# sch.net
KiCad netlist of a schematic drawn in Altium Designer
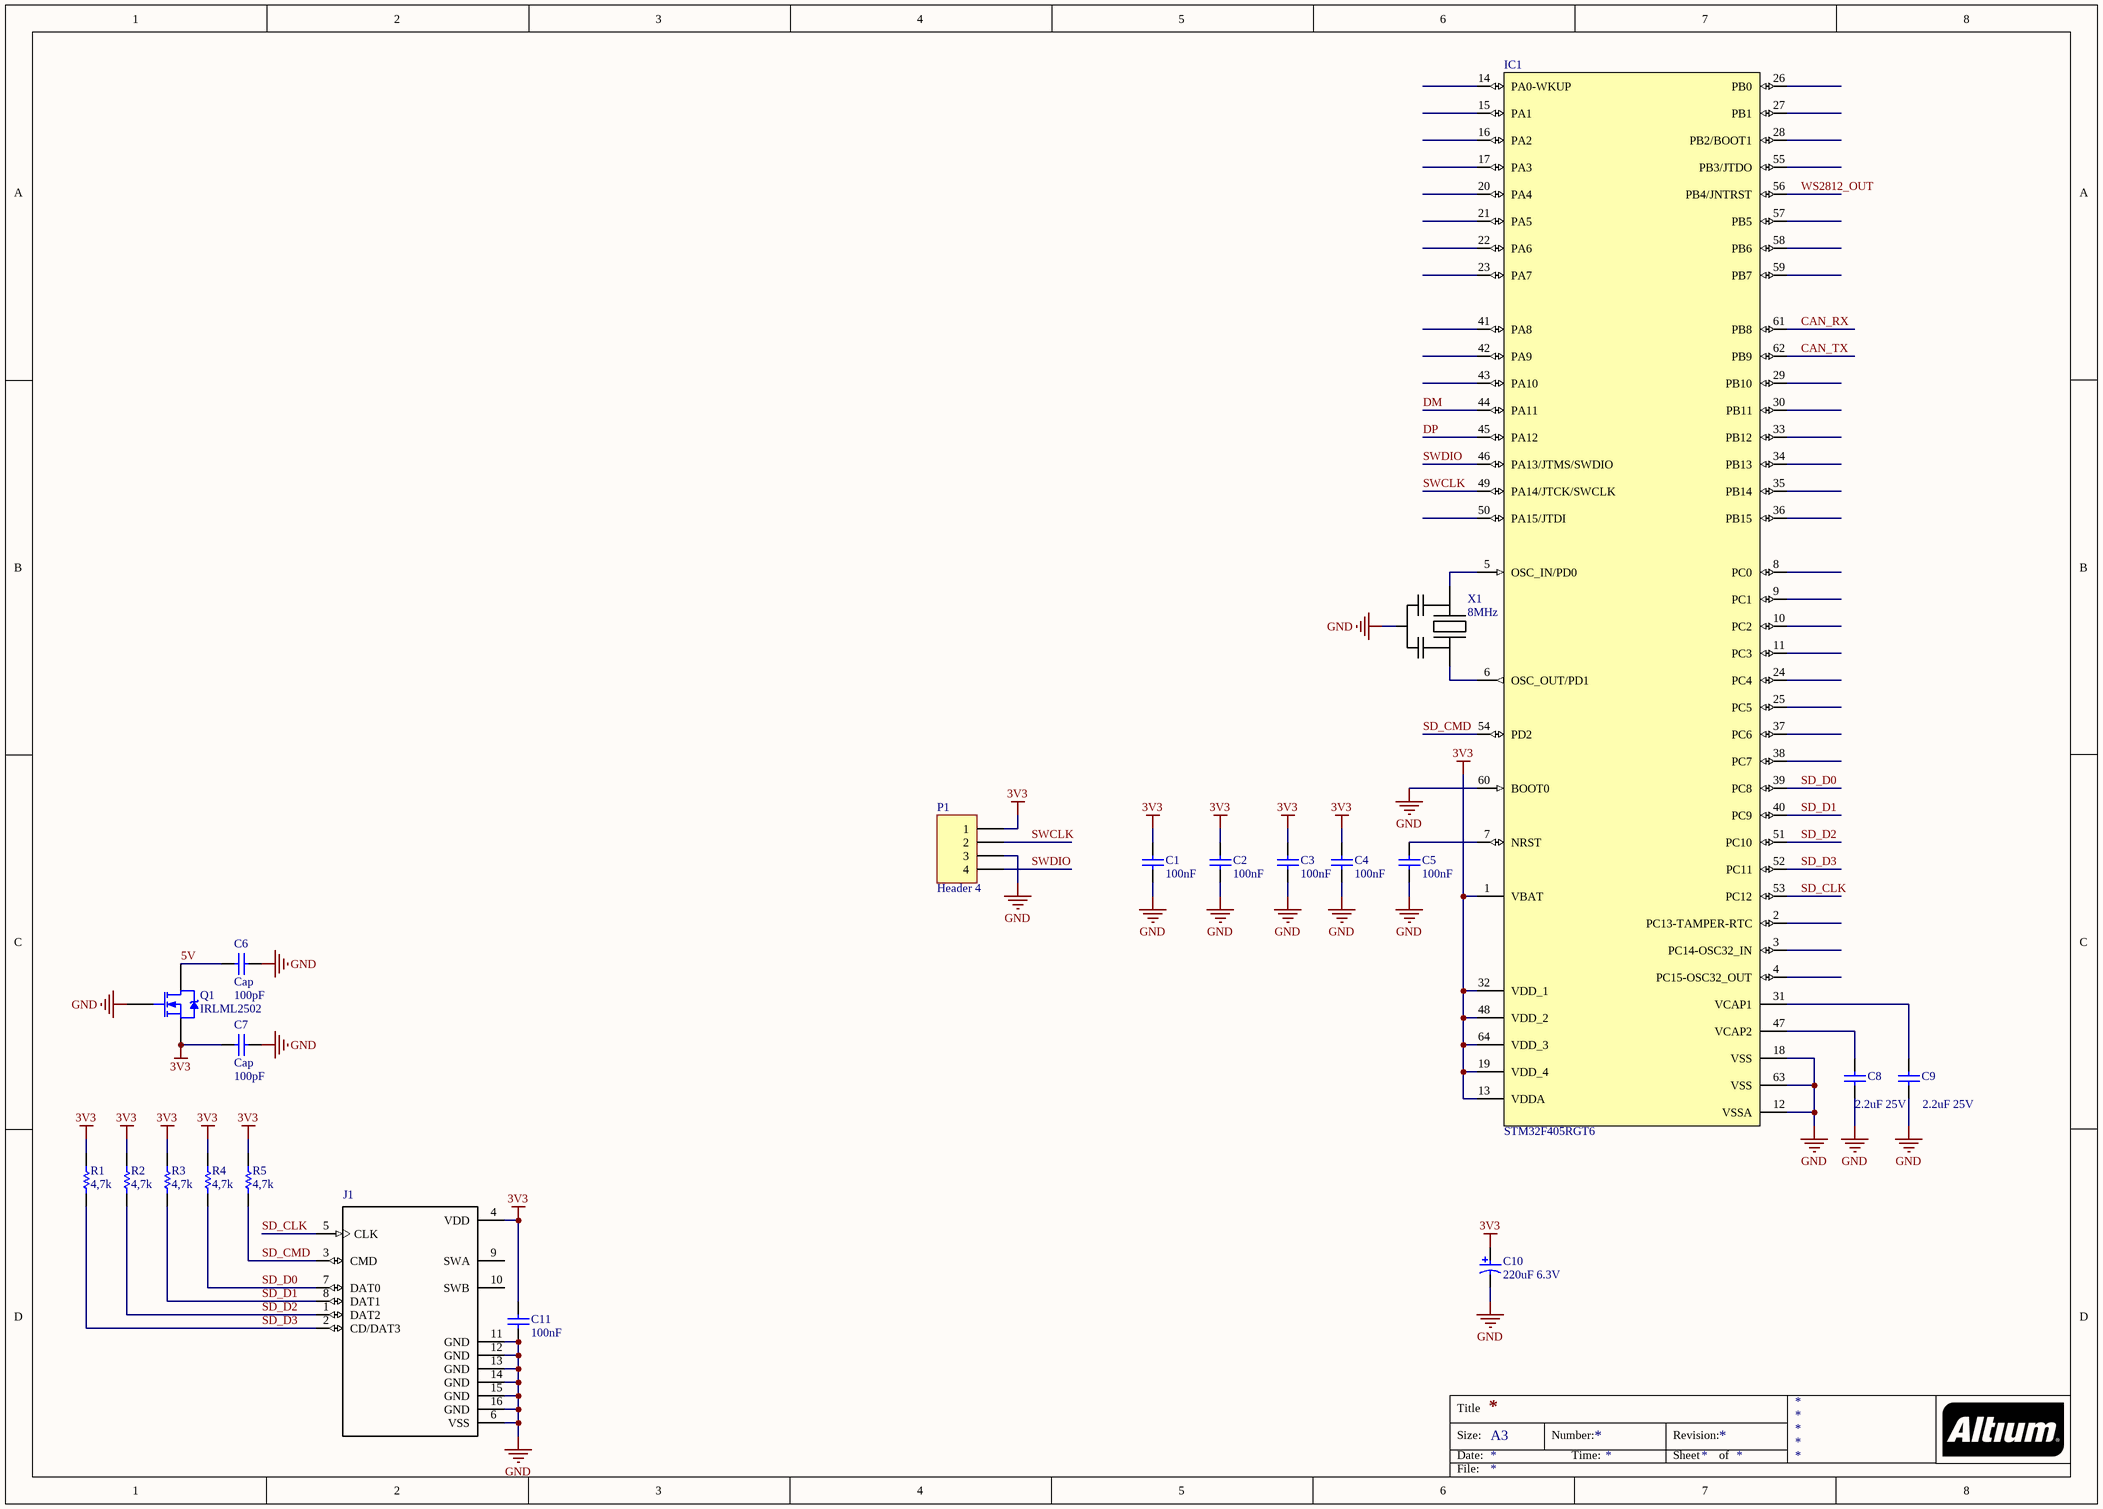
[diagram p0: sch.SchDoc]

(export (version "E")
  (design (tool "Eeschema 10.0.6"))
  (components
    (comp (ref "C1")
      (value "100nF")
      (footprint "RR_0603")
      (description "CAPACITOR CHIP")
      (fields (field (name "MANUFACTURER") "Vishay Vitramon"))
      (libsource (lib "RozumLibrary") (part "CAP-0603-104-25V"))
    )
    (comp (ref "C2")
      (value "100nF")
      (footprint "RR_0603")
      (description "CAPACITOR CHIP")
      (fields (field (name "MANUFACTURER") "Vishay Vitramon"))
      (libsource (lib "RozumLibrary") (part "CAP-0603-104-25V"))
    )
    (comp (ref "C3")
      (value "100nF")
      (footprint "RR_0603")
      (description "CAPACITOR CHIP")
      (fields (field (name "MANUFACTURER") "Vishay Vitramon"))
      (libsource (lib "RozumLibrary") (part "CAP-0603-104-25V"))
    )
    (comp (ref "C4")
      (value "100nF")
      (footprint "RR_0603")
      (description "CAPACITOR CHIP")
      (fields (field (name "MANUFACTURER") "Vishay Vitramon"))
      (libsource (lib "RozumLibrary") (part "CAP-0603-104-25V"))
    )
    (comp (ref "C5")
      (value "100nF")
      (footprint "RR_0603")
      (description "CAPACITOR CHIP")
      (fields (field (name "MANUFACTURER") "Vishay Vitramon"))
      (libsource (lib "RozumLibrary") (part "CAP-0603-104-25V"))
    )
    (comp (ref "C6")
      (value "Cap")
      (footprint "RC_1210_T1.8")
      (description "Capacitor")
      (fields (field (name "ALTIUM_VALUE") "100pF") (field (name "PUBLISHER") "Altium Limited"))
      (libsource (lib "Miscellaneous Devices") (part "Cap"))
    )
    (comp (ref "C7")
      (value "Cap")
      (footprint "RC_1210_T1.8")
      (description "Capacitor")
      (fields (field (name "ALTIUM_VALUE") "100pF") (field (name "PUBLISHER") "Altium Limited"))
      (libsource (lib "Miscellaneous Devices") (part "Cap"))
    )
    (comp (ref "C8")
      (value "2.2uF 25V")
      (footprint "RC_0603")
      (description "CAPACITOR CHIP")
      (fields (field (name "MANUFACTURER") "Murata"))
      (libsource (lib "RozumLibrary") (part "CAP-0603-225-25V"))
    )
    (comp (ref "C9")
      (value "2.2uF 25V")
      (footprint "RC_0603")
      (description "CAPACITOR CHIP")
      (fields (field (name "MANUFACTURER") "Murata"))
      (libsource (lib "RozumLibrary") (part "CAP-0603-225-25V"))
    )
    (comp (ref "C10")
      (value "220uF 6.3V")
      (footprint "RR_CAP-C")
      (description "CAPACITOR TANTAL CASE C")
      (fields (field (name "MANUFACTURER") "KEMET"))
      (libsource (lib "RozumLibrary") (part "CAP-TANT-C-227-6.3V"))
    )
    (comp (ref "C11")
      (value "100nF")
      (footprint "RR_0603")
      (description "CAPACITOR CHIP")
      (fields (field (name "MANUFACTURER") "Vishay Vitramon"))
      (libsource (lib "RozumLibrary") (part "CAP-0603-104-25V"))
    )
    (comp (ref "IC1")
      (value "STM32F405RGT6")
      (footprint "RR_LQFP-64_L_ROUND")
      (description "STM32 ARM-based 32-bit MCU")
      (fields (field (name "MANUFACTURER") "STMicroelectronics"))
      (libsource (lib "RozumLibrary") (part "STM32F405RGT6_RR"))
    )
    (comp (ref "J1")
      (value "MICROSD_2201778-1")
      (footprint "RR_CONN_MICROSD_TE_2201778-1")
      (description "MICRO SD PUSH PUSH LOW PROFILE TYPE")
      (fields (field (name "MANUFACTURER") "TE Connectivity AMP Connectors"))
      (libsource (lib "Schlib1") (part "MICROSD_2201778-1"))
    )
    (comp (ref "P1")
      (value "Header 4")
      (footprint "MHDR1X4")
      (description "Header, 4-Pin")
      (libsource (lib "Miscellaneous Connectors") (part "Header 4"))
    )
    (comp (ref "Q1")
      (value "IRLML2502")
      (footprint "RR_SOT-23")
      (description "MOSFET N-CH 20V 4.2A SOT-23-3")
      (fields (field (name "MANUFACTURER") "Infineon Technologies"))
      (libsource (lib "RozumLibrary") (part "IRLML2502"))
    )
    (comp (ref "R1")
      (value "4,7k")
      (footprint "RR_0603")
      (description "RESISTOR")
      (fields (field (name "MANUFACTURER") "Panasonic Electronic Components"))
      (libsource (lib "RozumLibrary") (part "RES-0603-4K7-5%"))
    )
    (comp (ref "R2")
      (value "4,7k")
      (footprint "RR_0603")
      (description "RESISTOR")
      (fields (field (name "MANUFACTURER") "Panasonic Electronic Components"))
      (libsource (lib "RozumLibrary") (part "RES-0603-4K7-5%"))
    )
    (comp (ref "R3")
      (value "4,7k")
      (footprint "RR_0603")
      (description "RESISTOR")
      (fields (field (name "MANUFACTURER") "Panasonic Electronic Components"))
      (libsource (lib "RozumLibrary") (part "RES-0603-4K7-5%"))
    )
    (comp (ref "R4")
      (value "4,7k")
      (footprint "RR_0603")
      (description "RESISTOR")
      (fields (field (name "MANUFACTURER") "Panasonic Electronic Components"))
      (libsource (lib "RozumLibrary") (part "RES-0603-4K7-5%"))
    )
    (comp (ref "R5")
      (value "4,7k")
      (footprint "RR_0603")
      (description "RESISTOR")
      (fields (field (name "MANUFACTURER") "Panasonic Electronic Components"))
      (libsource (lib "RozumLibrary") (part "RES-0603-4K7-5%"))
    )
    (comp (ref "X1")
      (value "8MHz")
      (footprint "RR_CRYSTAL_3.2X1.3")
      (description "XTAL 8.0000MHZ 33PF SMD")
      (fields (field (name "MANUFACTURER") "Murata Electronics"))
      (libsource (lib "RozumLibrary") (part "CSTCE8M00G55-R0"))
    )
  )
  (nets
    (net (code "1") (name "/5V") (class "Default")
      (node (ref "C6") (pin "2") (pinfunction "2_2") (pintype "passive"))
      (node (ref "Q1") (pin "3") (pinfunction "D_3") (pintype "passive"))
    )
    (net (code "2") (name "/CAN_RX") (class "Default")
      (node (ref "IC1") (pin "61") (pinfunction "PB8_61") (pintype "bidirectional"))
    )
    (net (code "3") (name "/CAN_TX") (class "Default")
      (node (ref "IC1") (pin "62") (pinfunction "PB9_62") (pintype "bidirectional"))
    )
    (net (code "4") (name "/DM") (class "Default")
      (node (ref "IC1") (pin "44") (pinfunction "PA11_44") (pintype "bidirectional"))
    )
    (net (code "5") (name "/DP") (class "Default")
      (node (ref "IC1") (pin "45") (pinfunction "PA12_45") (pintype "bidirectional"))
    )
    (net (code "6") (name "/SD_CLK") (class "Default")
      (node (ref "IC1") (pin "53") (pinfunction "PC12_53") (pintype "bidirectional"))
      (node (ref "J1") (pin "5") (pinfunction "CLK_5") (pintype "input"))
    )
    (net (code "7") (name "/SD_CMD") (class "Default")
      (node (ref "IC1") (pin "54") (pinfunction "PD2_54") (pintype "bidirectional"))
      (node (ref "J1") (pin "3") (pinfunction "CMD_3") (pintype "bidirectional"))
      (node (ref "R5") (pin "1") (pinfunction "1_1") (pintype "passive"))
    )
    (net (code "8") (name "/SD_D0") (class "Default")
      (node (ref "IC1") (pin "39") (pinfunction "PC8_39") (pintype "bidirectional"))
      (node (ref "J1") (pin "7") (pinfunction "DAT0_7") (pintype "bidirectional"))
      (node (ref "R4") (pin "1") (pinfunction "1_1") (pintype "passive"))
    )
    (net (code "9") (name "/SD_D1") (class "Default")
      (node (ref "IC1") (pin "40") (pinfunction "PC9_40") (pintype "bidirectional"))
      (node (ref "J1") (pin "8") (pinfunction "DAT1_8") (pintype "bidirectional"))
      (node (ref "R3") (pin "1") (pinfunction "1_1") (pintype "passive"))
    )
    (net (code "10") (name "/SD_D2") (class "Default")
      (node (ref "IC1") (pin "51") (pinfunction "PC10_51") (pintype "bidirectional"))
      (node (ref "J1") (pin "1") (pinfunction "DAT2_1") (pintype "bidirectional"))
      (node (ref "R2") (pin "1") (pinfunction "1_1") (pintype "passive"))
    )
    (net (code "11") (name "/SD_D3") (class "Default")
      (node (ref "IC1") (pin "52") (pinfunction "PC11_52") (pintype "bidirectional"))
      (node (ref "J1") (pin "2") (pinfunction "CD/DAT3_2") (pintype "bidirectional"))
      (node (ref "R1") (pin "1") (pinfunction "1_1") (pintype "passive"))
    )
    (net (code "12") (name "/SWCLK") (class "Default")
      (node (ref "IC1") (pin "49") (pinfunction "PA14/JTCK/SWCLK_49") (pintype "bidirectional"))
      (node (ref "P1") (pin "2") (pinfunction "2_2") (pintype "passive"))
    )
    (net (code "13") (name "/SWDIO") (class "Default")
      (node (ref "IC1") (pin "46") (pinfunction "PA13/JTMS/SWDIO_46") (pintype "bidirectional"))
      (node (ref "P1") (pin "4") (pinfunction "4_4") (pintype "passive"))
    )
    (net (code "14") (name "/WS2812_OUT") (class "Default")
      (node (ref "IC1") (pin "56") (pinfunction "PB4/JNTRST_56") (pintype "bidirectional"))
    )
    (net (code "15") (name "3V3") (class "Default")
      (node (ref "C1") (pin "2") (pinfunction "2_2") (pintype "passive"))
      (node (ref "C10") (pin "1") (pinfunction "1_1") (pintype "passive"))
      (node (ref "C11") (pin "1") (pinfunction "1_1") (pintype "passive"))
      (node (ref "C2") (pin "2") (pinfunction "2_2") (pintype "passive"))
      (node (ref "C3") (pin "2") (pinfunction "2_2") (pintype "passive"))
      (node (ref "C4") (pin "2") (pinfunction "2_2") (pintype "passive"))
      (node (ref "C7") (pin "2") (pinfunction "2_2") (pintype "passive"))
      (node (ref "IC1") (pin "1") (pinfunction "VBAT_1") (pintype "power_in"))
      (node (ref "IC1") (pin "13") (pinfunction "VDDA_13") (pintype "power_in"))
      (node (ref "IC1") (pin "19") (pinfunction "VDD_4_19") (pintype "power_in"))
      (node (ref "IC1") (pin "32") (pinfunction "VDD_1_32") (pintype "power_in"))
      (node (ref "IC1") (pin "48") (pinfunction "VDD_2_48") (pintype "power_in"))
      (node (ref "IC1") (pin "64") (pinfunction "VDD_3_64") (pintype "power_in"))
      (node (ref "J1") (pin "4") (pinfunction "VDD_4") (pintype "power_in"))
      (node (ref "P1") (pin "1") (pinfunction "1_1") (pintype "passive"))
      (node (ref "Q1") (pin "2") (pinfunction "S_2") (pintype "passive"))
      (node (ref "R1") (pin "2") (pinfunction "2_2") (pintype "passive"))
      (node (ref "R2") (pin "2") (pinfunction "2_2") (pintype "passive"))
      (node (ref "R3") (pin "2") (pinfunction "2_2") (pintype "passive"))
      (node (ref "R4") (pin "2") (pinfunction "2_2") (pintype "passive"))
      (node (ref "R5") (pin "2") (pinfunction "2_2") (pintype "passive"))
    )
    (net (code "16") (name "GND") (class "Default")
      (node (ref "C1") (pin "1") (pinfunction "1_1") (pintype "passive"))
      (node (ref "C10") (pin "2") (pinfunction "2_2") (pintype "passive"))
      (node (ref "C11") (pin "2") (pinfunction "2_2") (pintype "passive"))
      (node (ref "C2") (pin "1") (pinfunction "1_1") (pintype "passive"))
      (node (ref "C3") (pin "1") (pinfunction "1_1") (pintype "passive"))
      (node (ref "C4") (pin "1") (pinfunction "1_1") (pintype "passive"))
      (node (ref "C5") (pin "1") (pinfunction "1_1") (pintype "passive"))
      (node (ref "C6") (pin "1") (pinfunction "1_1") (pintype "passive"))
      (node (ref "C7") (pin "1") (pinfunction "1_1") (pintype "passive"))
      (node (ref "C8") (pin "2") (pinfunction "2_2") (pintype "passive"))
      (node (ref "C9") (pin "2") (pinfunction "2_2") (pintype "passive"))
      (node (ref "IC1") (pin "12") (pinfunction "VSSA_12") (pintype "power_in"))
      (node (ref "IC1") (pin "18") (pinfunction "VSS_18") (pintype "passive"))
      (node (ref "IC1") (pin "60") (pinfunction "BOOT0_60") (pintype "input"))
      (node (ref "IC1") (pin "63") (pinfunction "VSS_63") (pintype "power_in"))
      (node (ref "J1") (pin "11") (pinfunction "GND_11") (pintype "power_in"))
      (node (ref "J1") (pin "12") (pinfunction "GND_12") (pintype "power_in"))
      (node (ref "J1") (pin "13") (pinfunction "GND_13") (pintype "power_in"))
      (node (ref "J1") (pin "14") (pinfunction "GND_14") (pintype "power_in"))
      (node (ref "J1") (pin "15") (pinfunction "GND_15") (pintype "power_in"))
      (node (ref "J1") (pin "16") (pinfunction "GND_16") (pintype "power_in"))
      (node (ref "J1") (pin "6") (pinfunction "VSS_6") (pintype "power_in"))
      (node (ref "P1") (pin "3") (pinfunction "3_3") (pintype "passive"))
      (node (ref "Q1") (pin "1") (pinfunction "G_1") (pintype "passive"))
      (node (ref "X1") (pin "2") (pinfunction "GND_2") (pintype "passive"))
    )
    (net (code "17") (name "Net-(IC1-NRST)") (class "Default")
      (node (ref "C5") (pin "2") (pinfunction "2_2") (pintype "passive"))
      (node (ref "IC1") (pin "7") (pinfunction "NRST_7") (pintype "bidirectional"))
    )
    (net (code "18") (name "Net-(IC1-OSC_IN{slash}PD0)") (class "Default")
      (node (ref "IC1") (pin "5") (pinfunction "OSC_IN/PD0_5") (pintype "input"))
      (node (ref "X1") (pin "1") (pinfunction "X1_1") (pintype "passive"))
    )
    (net (code "19") (name "Net-(IC1-OSC_OUT{slash}PD1)") (class "Default")
      (node (ref "IC1") (pin "6") (pinfunction "OSC_OUT/PD1_6") (pintype "output"))
      (node (ref "X1") (pin "3") (pinfunction "X2_3") (pintype "passive"))
    )
    (net (code "20") (name "Net-(IC1-VCAP1)") (class "Default")
      (node (ref "C9") (pin "1") (pinfunction "1_1") (pintype "passive"))
      (node (ref "IC1") (pin "31") (pinfunction "VCAP1_31") (pintype "power_in"))
    )
    (net (code "21") (name "Net-(IC1-VCAP2)") (class "Default")
      (node (ref "C8") (pin "1") (pinfunction "1_1") (pintype "passive"))
      (node (ref "IC1") (pin "47") (pinfunction "VCAP2_47") (pintype "power_in"))
    )
    (net (code "22") (name "unconnected-(IC1-PA0-WKUP-Pad14)") (class "Default")
      (node (ref "IC1") (pin "14") (pinfunction "PA0-WKUP_14") (pintype "bidirectional"))
    )
    (net (code "23") (name "unconnected-(IC1-PA1-Pad15)") (class "Default")
      (node (ref "IC1") (pin "15") (pinfunction "PA1_15") (pintype "bidirectional"))
    )
    (net (code "24") (name "unconnected-(IC1-PA2-Pad16)") (class "Default")
      (node (ref "IC1") (pin "16") (pinfunction "PA2_16") (pintype "bidirectional"))
    )
    (net (code "25") (name "unconnected-(IC1-PA3-Pad17)") (class "Default")
      (node (ref "IC1") (pin "17") (pinfunction "PA3_17") (pintype "bidirectional"))
    )
    (net (code "26") (name "unconnected-(IC1-PA4-Pad20)") (class "Default")
      (node (ref "IC1") (pin "20") (pinfunction "PA4_20") (pintype "bidirectional"))
    )
    (net (code "27") (name "unconnected-(IC1-PA5-Pad21)") (class "Default")
      (node (ref "IC1") (pin "21") (pinfunction "PA5_21") (pintype "bidirectional"))
    )
    (net (code "28") (name "unconnected-(IC1-PA6-Pad22)") (class "Default")
      (node (ref "IC1") (pin "22") (pinfunction "PA6_22") (pintype "bidirectional"))
    )
    (net (code "29") (name "unconnected-(IC1-PA7-Pad23)") (class "Default")
      (node (ref "IC1") (pin "23") (pinfunction "PA7_23") (pintype "bidirectional"))
    )
    (net (code "30") (name "unconnected-(IC1-PA8-Pad41)") (class "Default")
      (node (ref "IC1") (pin "41") (pinfunction "PA8_41") (pintype "bidirectional"))
    )
    (net (code "31") (name "unconnected-(IC1-PA9-Pad42)") (class "Default")
      (node (ref "IC1") (pin "42") (pinfunction "PA9_42") (pintype "bidirectional"))
    )
    (net (code "32") (name "unconnected-(IC1-PA10-Pad43)") (class "Default")
      (node (ref "IC1") (pin "43") (pinfunction "PA10_43") (pintype "bidirectional"))
    )
    (net (code "33") (name "unconnected-(IC1-PA15{slash}JTDI-Pad50)") (class "Default")
      (node (ref "IC1") (pin "50") (pinfunction "PA15/JTDI_50") (pintype "bidirectional"))
    )
    (net (code "34") (name "unconnected-(IC1-PB0-Pad26)") (class "Default")
      (node (ref "IC1") (pin "26") (pinfunction "PB0_26") (pintype "bidirectional"))
    )
    (net (code "35") (name "unconnected-(IC1-PB1-Pad27)") (class "Default")
      (node (ref "IC1") (pin "27") (pinfunction "PB1_27") (pintype "bidirectional"))
    )
    (net (code "36") (name "unconnected-(IC1-PB2{slash}BOOT1-Pad28)") (class "Default")
      (node (ref "IC1") (pin "28") (pinfunction "PB2/BOOT1_28") (pintype "bidirectional"))
    )
    (net (code "37") (name "unconnected-(IC1-PB3{slash}JTDO-Pad55)") (class "Default")
      (node (ref "IC1") (pin "55") (pinfunction "PB3/JTDO_55") (pintype "bidirectional"))
    )
    (net (code "38") (name "unconnected-(IC1-PB5-Pad57)") (class "Default")
      (node (ref "IC1") (pin "57") (pinfunction "PB5_57") (pintype "bidirectional"))
    )
    (net (code "39") (name "unconnected-(IC1-PB6-Pad58)") (class "Default")
      (node (ref "IC1") (pin "58") (pinfunction "PB6_58") (pintype "bidirectional"))
    )
    (net (code "40") (name "unconnected-(IC1-PB7-Pad59)") (class "Default")
      (node (ref "IC1") (pin "59") (pinfunction "PB7_59") (pintype "bidirectional"))
    )
    (net (code "41") (name "unconnected-(IC1-PB10-Pad29)") (class "Default")
      (node (ref "IC1") (pin "29") (pinfunction "PB10_29") (pintype "bidirectional"))
    )
    (net (code "42") (name "unconnected-(IC1-PB11-Pad30)") (class "Default")
      (node (ref "IC1") (pin "30") (pinfunction "PB11_30") (pintype "bidirectional"))
    )
    (net (code "43") (name "unconnected-(IC1-PB12-Pad33)") (class "Default")
      (node (ref "IC1") (pin "33") (pinfunction "PB12_33") (pintype "bidirectional"))
    )
    (net (code "44") (name "unconnected-(IC1-PB13-Pad34)") (class "Default")
      (node (ref "IC1") (pin "34") (pinfunction "PB13_34") (pintype "bidirectional"))
    )
    (net (code "45") (name "unconnected-(IC1-PB14-Pad35)") (class "Default")
      (node (ref "IC1") (pin "35") (pinfunction "PB14_35") (pintype "bidirectional"))
    )
    (net (code "46") (name "unconnected-(IC1-PB15-Pad36)") (class "Default")
      (node (ref "IC1") (pin "36") (pinfunction "PB15_36") (pintype "bidirectional"))
    )
    (net (code "47") (name "unconnected-(IC1-PC0-Pad8)") (class "Default")
      (node (ref "IC1") (pin "8") (pinfunction "PC0_8") (pintype "bidirectional"))
    )
    (net (code "48") (name "unconnected-(IC1-PC1-Pad9)") (class "Default")
      (node (ref "IC1") (pin "9") (pinfunction "PC1_9") (pintype "bidirectional"))
    )
    (net (code "49") (name "unconnected-(IC1-PC2-Pad10)") (class "Default")
      (node (ref "IC1") (pin "10") (pinfunction "PC2_10") (pintype "bidirectional"))
    )
    (net (code "50") (name "unconnected-(IC1-PC3-Pad11)") (class "Default")
      (node (ref "IC1") (pin "11") (pinfunction "PC3_11") (pintype "bidirectional"))
    )
    (net (code "51") (name "unconnected-(IC1-PC4-Pad24)") (class "Default")
      (node (ref "IC1") (pin "24") (pinfunction "PC4_24") (pintype "bidirectional"))
    )
    (net (code "52") (name "unconnected-(IC1-PC5-Pad25)") (class "Default")
      (node (ref "IC1") (pin "25") (pinfunction "PC5_25") (pintype "bidirectional"))
    )
    (net (code "53") (name "unconnected-(IC1-PC6-Pad37)") (class "Default")
      (node (ref "IC1") (pin "37") (pinfunction "PC6_37") (pintype "bidirectional"))
    )
    (net (code "54") (name "unconnected-(IC1-PC7-Pad38)") (class "Default")
      (node (ref "IC1") (pin "38") (pinfunction "PC7_38") (pintype "bidirectional"))
    )
    (net (code "55") (name "unconnected-(IC1-PC13-TAMPER-RTC-Pad2)") (class "Default")
      (node (ref "IC1") (pin "2") (pinfunction "PC13-TAMPER-RTC_2") (pintype "bidirectional"))
    )
    (net (code "56") (name "unconnected-(IC1-PC14-OSC32_IN-Pad3)") (class "Default")
      (node (ref "IC1") (pin "3") (pinfunction "PC14-OSC32_IN_3") (pintype "bidirectional"))
    )
    (net (code "57") (name "unconnected-(IC1-PC15-OSC32_OUT-Pad4)") (class "Default")
      (node (ref "IC1") (pin "4") (pinfunction "PC15-OSC32_OUT_4") (pintype "bidirectional"))
    )
    (net (code "58") (name "unconnected-(J1-SWA-Pad9)") (class "Default")
      (node (ref "J1") (pin "9") (pinfunction "SWA_9") (pintype "passive"))
    )
    (net (code "59") (name "unconnected-(J1-SWB-Pad10)") (class "Default")
      (node (ref "J1") (pin "10") (pinfunction "SWB_10") (pintype "passive"))
    )
  )
)
